# hopper.net
KiCad netlist of a schematic drawn in EAGLE
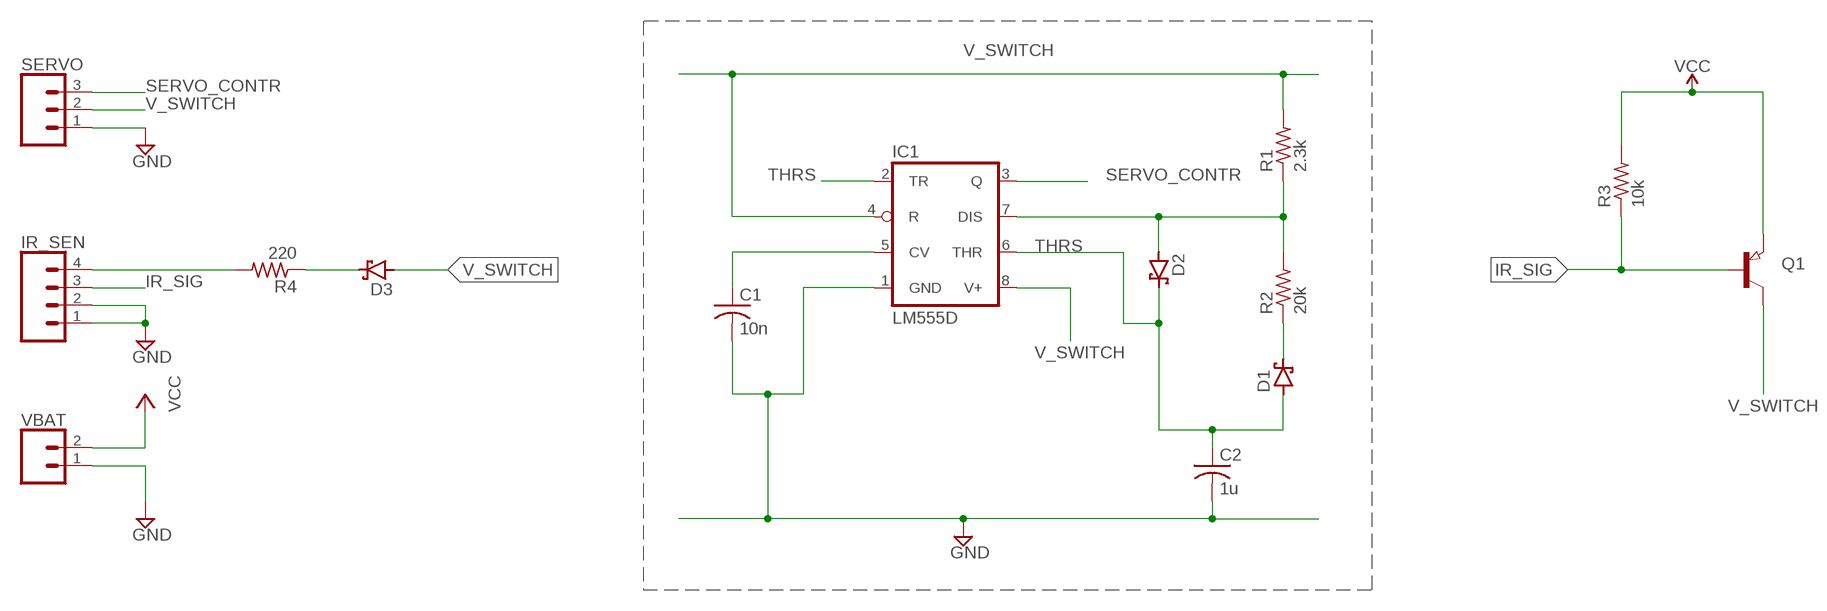
[diagram p0: schematic, sheet 1]

(export (version "E")
  (design (tool "Eeschema 10.0.6"))
  (components
    (comp (ref "C1")
      (value "10n")
      (footprint "eagle-import:C1206")
      (libsource (lib "eagle-import") (part "C-USC1206"))
    )
    (comp (ref "C2")
      (value "1u")
      (footprint "eagle-import:C1206")
      (libsource (lib "eagle-import") (part "C-USC1206"))
    )
    (comp (ref "D1")
      (value "SCHOTTKY-DIODESMD")
      (footprint "eagle-import:SMB")
      (libsource (lib "eagle-import") (part "SCHOTTKY-DIODESMD"))
    )
    (comp (ref "D2")
      (value "SCHOTTKY-DIODESMD")
      (footprint "eagle-import:SMB")
      (libsource (lib "eagle-import") (part "SCHOTTKY-DIODESMD"))
    )
    (comp (ref "D3")
      (value "SCHOTTKY-DIODESMD")
      (footprint "eagle-import:SMB")
      (libsource (lib "eagle-import") (part "SCHOTTKY-DIODESMD"))
    )
    (comp (ref "IC1")
      (value "LM555D")
      (footprint "eagle-import:SO08")
      (libsource (lib "eagle-import") (part "555DLM"))
    )
    (comp (ref "IR_SEN")
      (value "CONN_04")
      (footprint "eagle-import:1X04")
      (libsource (lib "eagle-import") (part "CONN_04"))
    )
    (comp (ref "Q1")
      (value "PNP-TRANSISTOR_SOT23")
      (footprint "eagle-import:SOT23")
      (libsource (lib "eagle-import") (part "PNP-TRANSISTOR_SOT23"))
    )
    (comp (ref "R1")
      (value "2.3k")
      (footprint "eagle-import:M1206")
      (libsource (lib "eagle-import") (part "R-US_M1206"))
    )
    (comp (ref "R2")
      (value "20k")
      (footprint "eagle-import:M1206")
      (libsource (lib "eagle-import") (part "R-US_M1206"))
    )
    (comp (ref "R3")
      (value "10k")
      (footprint "eagle-import:M1206")
      (libsource (lib "eagle-import") (part "R-US_M1206"))
    )
    (comp (ref "R4")
      (value "220")
      (footprint "eagle-import:M1206")
      (libsource (lib "eagle-import") (part "R-US_M1206"))
    )
    (comp (ref "SERVO")
      (value "CONN_03")
      (footprint "eagle-import:1X03")
      (libsource (lib "eagle-import") (part "CONN_03"))
    )
    (comp (ref "VBAT")
      (value "CONN_02-JST-2-PTH-NO_SILK")
      (footprint "eagle-import:JST-2-PTH-NS")
      (libsource (lib "eagle-import") (part "CONN_02-JST-2-PTH-NO_SILK"))
    )
  )
  (nets
    (net (code "1") (name "/SERVO_CONTR") (class "Default")
      (node (ref "IC1") (pin "3") (pinfunction "Q_3") (pintype "output"))
      (node (ref "SERVO") (pin "3") (pinfunction "3_3") (pintype "passive"))
    )
    (net (code "2") (name "/THRS") (class "Default")
      (node (ref "C2") (pin "1") (pinfunction "1_1") (pintype "passive"))
      (node (ref "D1") (pin "A") (pinfunction "A_A") (pintype "passive"))
      (node (ref "D2") (pin "C") (pinfunction "C_C") (pintype "passive"))
      (node (ref "IC1") (pin "2") (pinfunction "TR_2") (pintype "input"))
      (node (ref "IC1") (pin "6") (pinfunction "THR_6") (pintype "input"))
    )
    (net (code "3") (name "GND") (class "Default")
      (node (ref "C1") (pin "2") (pinfunction "2_2") (pintype "passive"))
      (node (ref "C2") (pin "2") (pinfunction "2_2") (pintype "passive"))
      (node (ref "IC1") (pin "1") (pinfunction "GND_1") (pintype "power_in"))
      (node (ref "IR_SEN") (pin "1") (pinfunction "1_1") (pintype "passive"))
      (node (ref "IR_SEN") (pin "2") (pinfunction "2_2") (pintype "passive"))
      (node (ref "SERVO") (pin "1") (pinfunction "1_1") (pintype "passive"))
      (node (ref "VBAT") (pin "1") (pinfunction "1_1") (pintype "passive"))
    )
    (net (code "4") (name "IR_SIG") (class "Default")
      (node (ref "IR_SEN") (pin "3") (pinfunction "3_3") (pintype "passive"))
      (node (ref "Q1") (pin "1") (pinfunction "B_1") (pintype "passive"))
      (node (ref "R3") (pin "1") (pinfunction "1_1") (pintype "passive"))
    )
    (net (code "5") (name "Net-(D1-PadC)") (class "Default")
      (node (ref "D1") (pin "C") (pinfunction "C_C") (pintype "passive"))
      (node (ref "R2") (pin "1") (pinfunction "1_1") (pintype "passive"))
    )
    (net (code "6") (name "Net-(D3-PadC)") (class "Default")
      (node (ref "D3") (pin "C") (pinfunction "C_C") (pintype "passive"))
      (node (ref "R4") (pin "1") (pinfunction "1_1") (pintype "passive"))
    )
    (net (code "7") (name "Net-(IC1-CV)") (class "Default")
      (node (ref "C1") (pin "1") (pinfunction "1_1") (pintype "passive"))
      (node (ref "IC1") (pin "5") (pinfunction "CV_5") (pintype "input"))
    )
    (net (code "8") (name "Net-(IC1-DIS)") (class "Default")
      (node (ref "D2") (pin "A") (pinfunction "A_A") (pintype "passive"))
      (node (ref "IC1") (pin "7") (pinfunction "DIS_7") (pintype "input"))
      (node (ref "R1") (pin "1") (pinfunction "1_1") (pintype "passive"))
      (node (ref "R2") (pin "2") (pinfunction "2_2") (pintype "passive"))
    )
    (net (code "9") (name "VCC") (class "Default")
      (node (ref "Q1") (pin "2") (pinfunction "E_2") (pintype "passive"))
      (node (ref "R3") (pin "2") (pinfunction "2_2") (pintype "passive"))
      (node (ref "VBAT") (pin "2") (pinfunction "2_2") (pintype "passive"))
    )
    (net (code "10") (name "V_SWITCH") (class "Default")
      (node (ref "D3") (pin "A") (pinfunction "A_A") (pintype "passive"))
      (node (ref "IC1") (pin "4") (pinfunction "R_4") (pintype "input"))
      (node (ref "IC1") (pin "8") (pinfunction "V+_8") (pintype "power_in"))
      (node (ref "IR_SEN") (pin "4") (pinfunction "4_4") (pintype "passive"))
      (node (ref "Q1") (pin "3") (pinfunction "C_3") (pintype "passive"))
      (node (ref "R1") (pin "2") (pinfunction "2_2") (pintype "passive"))
      (node (ref "R4") (pin "2") (pinfunction "2_2") (pintype "passive"))
      (node (ref "SERVO") (pin "2") (pinfunction "2_2") (pintype "passive"))
    )
  )
)
